# MainBoard.net
KiCad netlist of a schematic drawn in Altium Designer
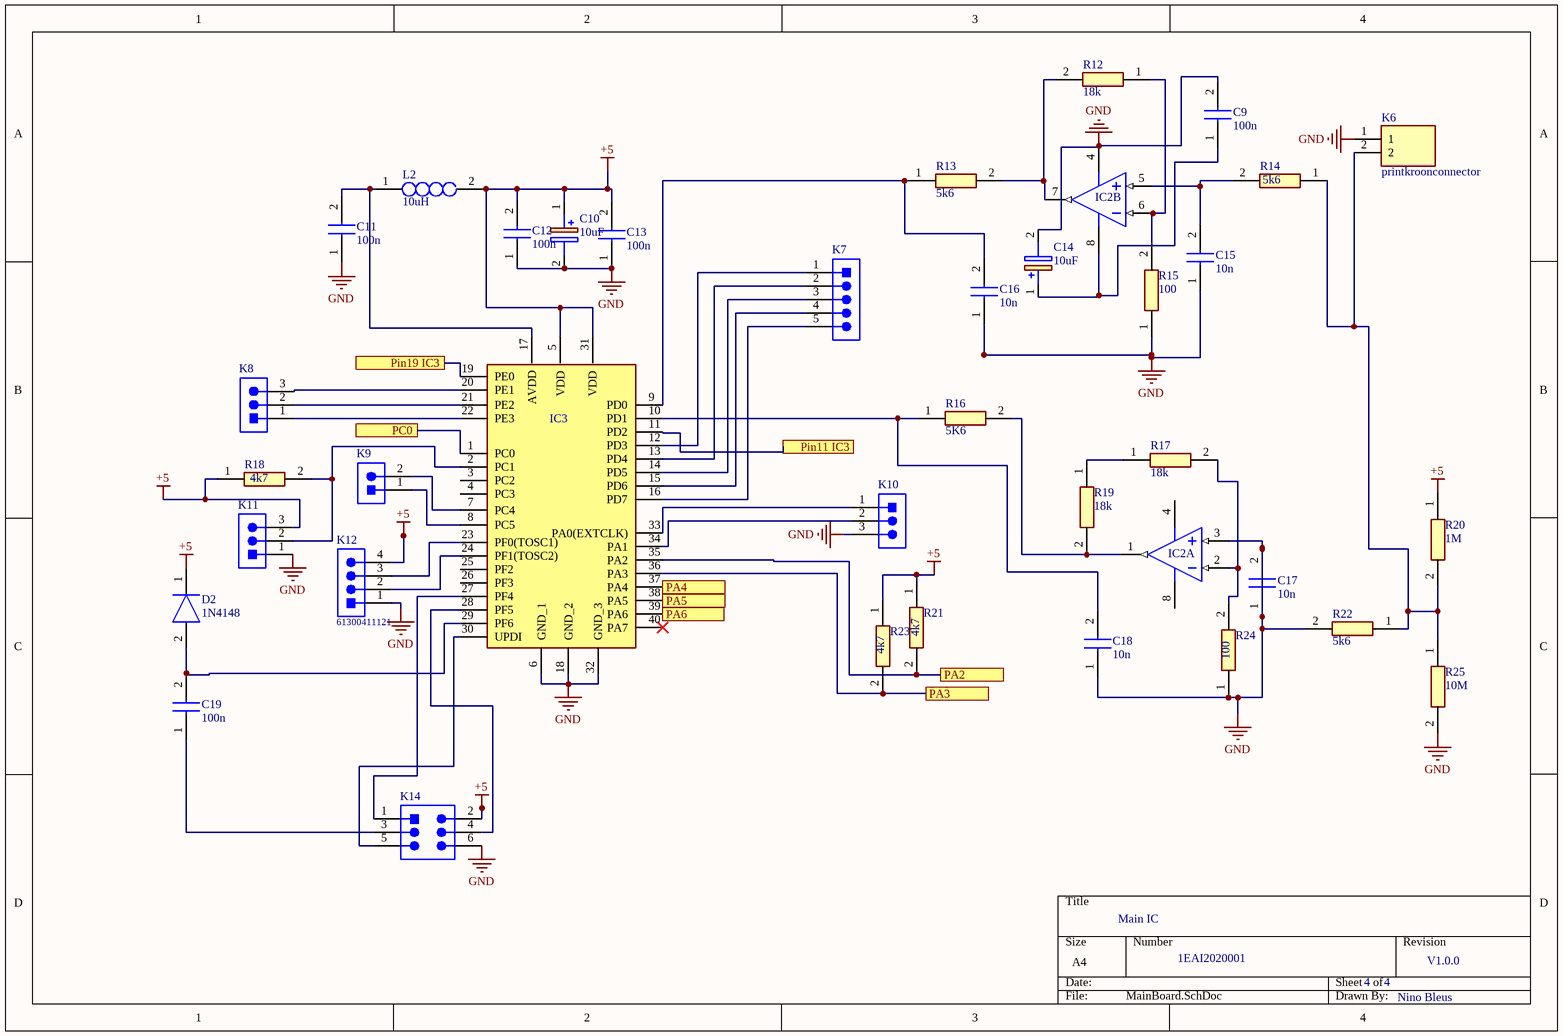
[diagram p0: MainBoard.SchDoc]

(export (version "E")
  (design (tool "Eeschema 10.0.6"))
  (components
    (comp (ref "C9")
      (value "100n")
      (footprint "SamacSys:CAPC2012X88N")
      (description "Capacitor")
      (fields (field (name "MANUFACTURER_PART_NUMBER") "C0805C103K5RACTU"))
      (libsource (lib "Schlib_soldeerbout") (part "0805 SMD capaciteit"))
    )
    (comp (ref "C10")
      (value "10uF")
      (footprint "SamacSys:CAPPRD250W45D630H850")
      (description "Capacitor Polarised")
      (fields (field (name "MANUFACTURER_PART_NUMBER") "ESS106M050AE2AA"))
      (libsource (lib "Schlib_soldeerbout") (part "10uF Capaciteit"))
    )
    (comp (ref "C11")
      (value "100n")
      (footprint "SamacSys:CAPC2012X88N")
      (description "Capacitor")
      (fields (field (name "MANUFACTURER_PART_NUMBER") "C0805C103K5RACTU"))
      (libsource (lib "Schlib_soldeerbout") (part "0805 SMD capaciteit"))
    )
    (comp (ref "C12")
      (value "100n")
      (footprint "SamacSys:CAPC2012X88N")
      (description "Capacitor")
      (fields (field (name "MANUFACTURER_PART_NUMBER") "C0805C103K5RACTU"))
      (libsource (lib "Schlib_soldeerbout") (part "0805 SMD capaciteit"))
    )
    (comp (ref "C13")
      (value "100n")
      (footprint "SamacSys:CAPC2012X88N")
      (description "Capacitor")
      (fields (field (name "MANUFACTURER_PART_NUMBER") "C0805C103K5RACTU"))
      (libsource (lib "Schlib_soldeerbout") (part "0805 SMD capaciteit"))
    )
    (comp (ref "C14")
      (value "10uF")
      (footprint "SamacSys:CAPPRD250W45D630H850")
      (description "Capacitor Polarised")
      (fields (field (name "MANUFACTURER_PART_NUMBER") "ESS106M050AE2AA"))
      (libsource (lib "") (part "10uF Capaciteit_1"))
    )
    (comp (ref "C15")
      (value "10n")
      (footprint "SamacSys:CAPC2012X88N")
      (description "Capacitor")
      (fields (field (name "MANUFACTURER_PART_NUMBER") "C0805C103K5RACTU"))
      (libsource (lib "Schlib_soldeerbout") (part "0805 SMD capaciteit"))
    )
    (comp (ref "C16")
      (value "10n")
      (footprint "SamacSys:CAPC2012X88N")
      (description "Capacitor")
      (fields (field (name "MANUFACTURER_PART_NUMBER") "C0805C103K5RACTU"))
      (libsource (lib "Schlib_soldeerbout") (part "0805 SMD capaciteit"))
    )
    (comp (ref "C17")
      (value "10n")
      (footprint "SamacSys:CAPC2012X88N")
      (description "Capacitor")
      (fields (field (name "MANUFACTURER_PART_NUMBER") "C0805C103K5RACTU"))
      (libsource (lib "Schlib_soldeerbout") (part "0805 SMD capaciteit"))
    )
    (comp (ref "C18")
      (value "10n")
      (footprint "SamacSys:CAPC2012X88N")
      (description "Capacitor")
      (fields (field (name "MANUFACTURER_PART_NUMBER") "C0805C103K5RACTU"))
      (libsource (lib "Schlib_soldeerbout") (part "0805 SMD capaciteit"))
    )
    (comp (ref "C19")
      (value "100n")
      (footprint "SamacSys:CAPC2012X88N")
      (description "Capacitor")
      (fields (field (name "MANUFACTURER_PART_NUMBER") "C0805C103K5RACTU"))
      (libsource (lib "Schlib_soldeerbout") (part "0805 SMD capaciteit"))
    )
    (comp (ref "D2")
      (value "1N4148")
      (footprint "SamacSys:DIOAD1165W56L425D185")
      (description "Diode")
      (libsource (lib "SamacSys") (part "1N4148"))
    )
    (comp (ref "IC2")
      (value "MCP6002-E/P")
      (footprint "PDIP300-P8")
      (description "None")
      (libsource (lib "Altium Content Vault") (part "AMP-OPA-MCP6002-IL8"))
    )
    (comp (ref "IC3")
      (value "ATMEGA4809-PF")
      (footprint "SamacSys:DIP1543W58P254L5175H635Q40N")
      (description "Integrated Circuit")
      (fields (field (name "MOUSER2 PART NUMBER") "556-ATMEGA4809-PF"))
      (libsource (lib "Schlib_soldeerbout") (part "ATMEGA4809-PF"))
    )
    (comp (ref "K6")
      (value "printkroonconnector")
      (footprint "SamacSys:1729128")
      (description "Connector")
      (fields (field (name "MANUFACTURER_PART_NUMBER") "1729128"))
      (libsource (lib "Schlib_soldeerbout") (part "printkroonconnector"))
    )
    (comp (ref "K7")
      (value "61300511121")
      (footprint "61300511121")
      (description "WR-PHD Pin Header, THT, pitch 2.54mm, Single Row, Vertical, 5p")
      (fields (field (name "MANUFACTURER") "Wurth Elektronik"))
      (libsource (lib "WR-PHD_Pin Header") (part "61300511121"))
    )
    (comp (ref "K8")
      (value "61300311121")
      (footprint "61300311121")
      (description "WR-PHD Pin Header, THT, pitch 2.54mm, Single Row, Vertical, 3p")
      (fields (field (name "MANUFACTURER") "Wurth Elektronik"))
      (libsource (lib "") (part "61300311121_1"))
    )
    (comp (ref "K9")
      (value "61300211121")
      (footprint "61300211121")
      (description "WR-PHD Pin Header, THT, pitch 2.54mm, Single Row, Vertical, 2p")
      (fields (field (name "MANUFACTURER") "Wurth Elektronik"))
      (libsource (lib "WR-PHD_Pin Header") (part "61300211121"))
    )
    (comp (ref "K10")
      (value "61300311121")
      (footprint "61300311121")
      (description "WR-PHD Pin Header, THT, pitch 2.54mm, Single Row, Vertical, 3p")
      (fields (field (name "MANUFACTURER") "Wurth Elektronik"))
      (libsource (lib "WR-PHD_Pin Header") (part "61300311121"))
    )
    (comp (ref "K11")
      (value "61300311121")
      (footprint "61300311121")
      (description "WR-PHD Pin Header, THT, pitch 2.54mm, Single Row, Vertical, 3p")
      (fields (field (name "MANUFACTURER") "Wurth Elektronik"))
      (libsource (lib "") (part "61300311121_1"))
    )
    (comp (ref "K12")
      (value "61300411121")
      (footprint "61300411121")
      (description "WR-PHD Pin Header, THT, pitch 2.54mm, Single Row, Vertical, 4p")
      (fields (field (name "MANUFACTURER") "Wurth Elektronik"))
      (libsource (lib "WR-PHD_Pin Header") (part "61300411121"))
    )
    (comp (ref "K14")
      (value "61300621121")
      (footprint "61300621121")
      (description "WR-PHD Pin Header, THT, pitch 2.54mm, Dual Row, Vertical, 6p")
      (fields (field (name "MANUFACTURER") "Wurth Elektronik"))
      (libsource (lib "WR-PHD_Pin Header") (part "61300621121"))
    )
    (comp (ref "L2")
      (value "10uH")
      (footprint "SamacSys:INDAD1827W51L711D279")
      (description "Inductor")
      (fields
        (field (name "MOUSER2 PART NUMBER") "542-78F100-RC")
        (field (name "MANUFACTURER_PART_NUMBER") "78F100J-RC")
      )
      (libsource (lib "Schlib_soldeerbout") (part "78F100J-RC"))
    )
    (comp (ref "R12")
      (value "18k")
      (footprint "SamacSys:RESC2012X65N")
      (description "Resistor")
      (fields (field (name "MANUFACTURER_PART_NUMBER") "ESR10EZPJ183"))
      (libsource (lib "") (part "ESR10EZPJ183_2"))
    )
    (comp (ref "R13")
      (value "5k6")
      (footprint "SamacSys:RESC2012X65N")
      (description "Resistor")
      (fields (field (name "MANUFACTURER_PART_NUMBER") "ESR10EZPJ183"))
      (libsource (lib "Schlib_soldeerbout") (part "ESR10EZPJ183"))
    )
    (comp (ref "R14")
      (value "5k6")
      (footprint "SamacSys:RESC2012X65N")
      (description "Resistor")
      (fields (field (name "MANUFACTURER_PART_NUMBER") "ESR10EZPJ183"))
      (libsource (lib "") (part "ESR10EZPJ183_2"))
    )
    (comp (ref "R15")
      (value "100")
      (footprint "SamacSys:RESC2012X65N")
      (description "Resistor")
      (fields (field (name "MANUFACTURER_PART_NUMBER") "ESR10EZPJ183"))
      (libsource (lib "") (part "ESR10EZPJ183_3"))
    )
    (comp (ref "R16")
      (value "5K6")
      (footprint "SamacSys:RESC2012X65N")
      (description "Resistor")
      (fields (field (name "MANUFACTURER_PART_NUMBER") "ESR10EZPJ183"))
      (libsource (lib "Schlib_soldeerbout") (part "ESR10EZPJ183"))
    )
    (comp (ref "R17")
      (value "18k")
      (footprint "SamacSys:RESC2012X65N")
      (description "Resistor")
      (fields (field (name "MANUFACTURER_PART_NUMBER") "ESR10EZPJ183"))
      (libsource (lib "Schlib_soldeerbout") (part "ESR10EZPJ183"))
    )
    (comp (ref "R18")
      (value "4k7")
      (footprint "SamacSys:RESC2012X65N")
      (description "Resistor")
      (fields (field (name "MANUFACTURER_PART_NUMBER") "ESR10EZPJ183"))
      (libsource (lib "Schlib_soldeerbout") (part "ESR10EZPJ183"))
    )
    (comp (ref "R19")
      (value "18k")
      (footprint "SamacSys:RESC2012X65N")
      (description "Resistor")
      (fields (field (name "MANUFACTURER_PART_NUMBER") "ESR10EZPJ183"))
      (libsource (lib "") (part "ESR10EZPJ183_1"))
    )
    (comp (ref "R20")
      (value "1M")
      (footprint "SamacSys:RESC2012X65N")
      (description "Resistor")
      (fields (field (name "MANUFACTURER_PART_NUMBER") "ESR10EZPJ183"))
      (libsource (lib "") (part "ESR10EZPJ183_1"))
    )
    (comp (ref "R21")
      (value "4k7")
      (footprint "SamacSys:RESC2012X65N")
      (description "Resistor")
      (fields (field (name "MANUFACTURER_PART_NUMBER") "ESR10EZPJ183"))
      (libsource (lib "") (part "ESR10EZPJ183_1"))
    )
    (comp (ref "R22")
      (value "5k6")
      (footprint "SamacSys:RESC2012X65N")
      (description "Resistor")
      (fields (field (name "MANUFACTURER_PART_NUMBER") "ESR10EZPJ183"))
      (libsource (lib "") (part "ESR10EZPJ183_2"))
    )
    (comp (ref "R23")
      (value "4k7")
      (footprint "SamacSys:RESC2012X65N")
      (description "Resistor")
      (fields (field (name "MANUFACTURER_PART_NUMBER") "ESR10EZPJ183"))
      (libsource (lib "") (part "ESR10EZPJ183_1"))
    )
    (comp (ref "R24")
      (value "100")
      (footprint "SamacSys:RESC2012X65N")
      (description "Resistor")
      (fields (field (name "MANUFACTURER_PART_NUMBER") "ESR10EZPJ183"))
      (libsource (lib "") (part "ESR10EZPJ183_3"))
    )
    (comp (ref "R25")
      (value "10M")
      (footprint "SamacSys:RESC2012X65N")
      (description "Resistor")
      (fields (field (name "MANUFACTURER_PART_NUMBER") "ESR10EZPJ183"))
      (libsource (lib "") (part "ESR10EZPJ183_1"))
    )
  )
  (nets
    (net (code "1") (name "+5") (class "Default")
      (node (ref "C10") (pin "1") (pinfunction "+_1") (pintype "passive"))
      (node (ref "C12") (pin "2") (pinfunction "2_2") (pintype "passive"))
      (node (ref "C13") (pin "2") (pinfunction "2_2") (pintype "passive"))
      (node (ref "D2") (pin "1") (pinfunction "K_1") (pintype "passive"))
      (node (ref "IC3") (pin "31") (pinfunction "VDD_31") (pintype "passive"))
      (node (ref "IC3") (pin "5") (pinfunction "VDD_5") (pintype "passive"))
      (node (ref "K11") (pin "3") (pinfunction "3_3") (pintype "passive"))
      (node (ref "K12") (pin "4") (pinfunction "4_4") (pintype "passive"))
      (node (ref "K14") (pin "2") (pinfunction "2_2") (pintype "passive"))
      (node (ref "L2") (pin "2") (pinfunction "2_2") (pintype "passive"))
      (node (ref "R18") (pin "1") (pinfunction "1_1") (pintype "passive"))
      (node (ref "R20") (pin "1") (pinfunction "1_1") (pintype "passive"))
      (node (ref "R21") (pin "1") (pinfunction "1_1") (pintype "passive"))
      (node (ref "R23") (pin "1") (pinfunction "1_1") (pintype "passive"))
    )
    (net (code "2") (name "/PA2") (class "Default")
      (node (ref "IC3") (pin "35") (pinfunction "PA2_35") (pintype "passive"))
      (node (ref "R21") (pin "2") (pinfunction "2_2") (pintype "passive"))
    )
    (net (code "3") (name "/PA3") (class "Default")
      (node (ref "IC3") (pin "36") (pinfunction "PA3_36") (pintype "passive"))
      (node (ref "R23") (pin "2") (pinfunction "2_2") (pintype "passive"))
    )
    (net (code "4") (name "/PA4") (class "Default")
      (node (ref "IC3") (pin "37") (pinfunction "PA4_37") (pintype "passive"))
    )
    (net (code "5") (name "/PA5") (class "Default")
      (node (ref "IC3") (pin "38") (pinfunction "PA5_38") (pintype "passive"))
    )
    (net (code "6") (name "/PA6") (class "Default")
      (node (ref "IC3") (pin "39") (pinfunction "PA6_39") (pintype "passive"))
    )
    (net (code "7") (name "/PC0") (class "Default")
      (node (ref "IC3") (pin "1") (pinfunction "PC0_1") (pintype "passive"))
    )
    (net (code "8") (name "/Pin11 IC3") (class "Default")
      (node (ref "IC3") (pin "11") (pinfunction "PD2_11") (pintype "passive"))
    )
    (net (code "9") (name "/Pin19 IC3") (class "Default")
      (node (ref "IC3") (pin "19") (pinfunction "PE0_19") (pintype "passive"))
    )
    (net (code "10") (name "GND") (class "Default")
      (node (ref "C10") (pin "2") (pinfunction "-_2") (pintype "passive"))
      (node (ref "C11") (pin "1") (pinfunction "1_1") (pintype "passive"))
      (node (ref "C12") (pin "1") (pinfunction "1_1") (pintype "passive"))
      (node (ref "C13") (pin "1") (pinfunction "1_1") (pintype "passive"))
      (node (ref "C14") (pin "2") (pinfunction "-_2") (pintype "passive"))
      (node (ref "C15") (pin "1") (pinfunction "1_1") (pintype "passive"))
      (node (ref "C16") (pin "1") (pinfunction "1_1") (pintype "passive"))
      (node (ref "C17") (pin "1") (pinfunction "1_1") (pintype "passive"))
      (node (ref "C17") (pin "2") (pinfunction "2_2") (pintype "passive"))
      (node (ref "C18") (pin "1") (pinfunction "1_1") (pintype "passive"))
      (node (ref "C9") (pin "2") (pinfunction "2_2") (pintype "passive"))
      (node (ref "IC2") (pin "3") (pinfunction "VINA+_3") (pintype "input"))
      (node (ref "IC2") (pin "4") (pinfunction "VSS_4") (pintype "power_in"))
      (node (ref "IC3") (pin "18") (pinfunction "GND_2_18") (pintype "passive"))
      (node (ref "IC3") (pin "32") (pinfunction "GND_3_32") (pintype "passive"))
      (node (ref "IC3") (pin "6") (pinfunction "GND_1_6") (pintype "passive"))
      (node (ref "K10") (pin "3") (pinfunction "3_3") (pintype "passive"))
      (node (ref "K11") (pin "1") (pinfunction "1_1") (pintype "passive"))
      (node (ref "K12") (pin "1") (pinfunction "1_1") (pintype "passive"))
      (node (ref "K14") (pin "6") (pinfunction "6_6") (pintype "passive"))
      (node (ref "K6") (pin "1") (pinfunction "1_1") (pintype "passive"))
      (node (ref "R15") (pin "1") (pinfunction "1_1") (pintype "passive"))
      (node (ref "R22") (pin "2") (pinfunction "2_2") (pintype "passive"))
      (node (ref "R24") (pin "1") (pinfunction "1_1") (pintype "passive"))
      (node (ref "R25") (pin "2") (pinfunction "2_2") (pintype "passive"))
    )
    (net (code "11") (name "Net-(C14-+)") (class "Default")
      (node (ref "C14") (pin "1") (pinfunction "+_1") (pintype "passive"))
      (node (ref "C9") (pin "1") (pinfunction "1_1") (pintype "passive"))
      (node (ref "IC2") (pin "8") (pinfunction "VDD_8") (pintype "power_in"))
    )
    (net (code "12") (name "Net-(C19-Pad1)") (class "Default")
      (node (ref "C19") (pin "1") (pinfunction "1_1") (pintype "passive"))
      (node (ref "K14") (pin "3") (pinfunction "3_3") (pintype "passive"))
    )
    (net (code "13") (name "Net-(D2-A)") (class "Default")
      (node (ref "C19") (pin "2") (pinfunction "2_2") (pintype "passive"))
      (node (ref "D2") (pin "2") (pinfunction "A_2") (pintype "passive"))
      (node (ref "IC3") (pin "29") (pinfunction "PF6_29") (pintype "passive"))
    )
    (net (code "14") (name "Net-(IC2A-VINA-)") (class "Default")
      (node (ref "IC2") (pin "2") (pinfunction "VINA-_2") (pintype "input"))
      (node (ref "R17") (pin "2") (pinfunction "2_2") (pintype "passive"))
      (node (ref "R24") (pin "2") (pinfunction "2_2") (pintype "passive"))
    )
    (net (code "15") (name "Net-(IC2A-VOUTA)") (class "Default")
      (node (ref "IC2") (pin "1") (pinfunction "VOUTA_1") (pintype "output"))
      (node (ref "R16") (pin "2") (pinfunction "2_2") (pintype "passive"))
      (node (ref "R19") (pin "2") (pinfunction "2_2") (pintype "passive"))
    )
    (net (code "16") (name "Net-(IC2B-VINB+)") (class "Default")
      (node (ref "C15") (pin "2") (pinfunction "2_2") (pintype "passive"))
      (node (ref "IC2") (pin "5") (pinfunction "VINB+_5") (pintype "input"))
      (node (ref "R14") (pin "2") (pinfunction "2_2") (pintype "passive"))
    )
    (net (code "17") (name "Net-(IC2B-VINB-)") (class "Default")
      (node (ref "IC2") (pin "6") (pinfunction "VINB-_6") (pintype "input"))
      (node (ref "R12") (pin "1") (pinfunction "1_1") (pintype "passive"))
      (node (ref "R15") (pin "2") (pinfunction "2_2") (pintype "passive"))
    )
    (net (code "18") (name "Net-(IC2B-VOUTB)") (class "Default")
      (node (ref "IC2") (pin "7") (pinfunction "VOUTB_7") (pintype "output"))
      (node (ref "R12") (pin "2") (pinfunction "2_2") (pintype "passive"))
      (node (ref "R13") (pin "2") (pinfunction "2_2") (pintype "passive"))
    )
    (net (code "19") (name "Net-(IC3-AVDD)") (class "Default")
      (node (ref "C11") (pin "2") (pinfunction "2_2") (pintype "passive"))
      (node (ref "IC3") (pin "17") (pinfunction "AVDD_17") (pintype "passive"))
      (node (ref "L2") (pin "1") (pinfunction "1_1") (pintype "passive"))
    )
    (net (code "20") (name "Net-(IC3-PA0(EXTCLK))") (class "Default")
      (node (ref "IC3") (pin "33") (pinfunction "PA0(EXTCLK)_33") (pintype "passive"))
      (node (ref "K10") (pin "1") (pinfunction "1_1") (pintype "passive"))
    )
    (net (code "21") (name "Net-(IC3-PA1)") (class "Default")
      (node (ref "IC3") (pin "34") (pinfunction "PA1_34") (pintype "passive"))
      (node (ref "K10") (pin "2") (pinfunction "2_2") (pintype "passive"))
    )
    (net (code "22") (name "Net-(IC3-PC1)") (class "Default")
      (node (ref "IC3") (pin "2") (pinfunction "PC1_2") (pintype "passive"))
      (node (ref "K11") (pin "2") (pinfunction "2_2") (pintype "passive"))
      (node (ref "R18") (pin "2") (pinfunction "2_2") (pintype "passive"))
    )
    (net (code "23") (name "Net-(IC3-PC4)") (class "Default")
      (node (ref "IC3") (pin "7") (pinfunction "PC4_7") (pintype "passive"))
      (node (ref "K9") (pin "2") (pinfunction "2_2") (pintype "passive"))
    )
    (net (code "24") (name "Net-(IC3-PC5)") (class "Default")
      (node (ref "IC3") (pin "8") (pinfunction "PC5_8") (pintype "passive"))
      (node (ref "K9") (pin "1") (pinfunction "1_1") (pintype "passive"))
    )
    (net (code "25") (name "Net-(IC3-PD0)") (class "Default")
      (node (ref "C16") (pin "2") (pinfunction "2_2") (pintype "passive"))
      (node (ref "IC3") (pin "9") (pinfunction "PD0_9") (pintype "passive"))
      (node (ref "R13") (pin "1") (pinfunction "1_1") (pintype "passive"))
    )
    (net (code "26") (name "Net-(IC3-PD1)") (class "Default")
      (node (ref "C18") (pin "2") (pinfunction "2_2") (pintype "passive"))
      (node (ref "IC3") (pin "10") (pinfunction "PD1_10") (pintype "passive"))
      (node (ref "R16") (pin "1") (pinfunction "1_1") (pintype "passive"))
    )
    (net (code "27") (name "Net-(IC3-PD3)") (class "Default")
      (node (ref "IC3") (pin "12") (pinfunction "PD3_12") (pintype "passive"))
      (node (ref "K7") (pin "1") (pinfunction "1_1") (pintype "passive"))
    )
    (net (code "28") (name "Net-(IC3-PD4)") (class "Default")
      (node (ref "IC3") (pin "13") (pinfunction "PD4_13") (pintype "passive"))
      (node (ref "K7") (pin "2") (pinfunction "2_2") (pintype "passive"))
    )
    (net (code "29") (name "Net-(IC3-PD5)") (class "Default")
      (node (ref "IC3") (pin "14") (pinfunction "PD5_14") (pintype "passive"))
      (node (ref "K7") (pin "3") (pinfunction "3_3") (pintype "passive"))
    )
    (net (code "30") (name "Net-(IC3-PD6)") (class "Default")
      (node (ref "IC3") (pin "15") (pinfunction "PD6_15") (pintype "passive"))
      (node (ref "K7") (pin "4") (pinfunction "4_4") (pintype "passive"))
    )
    (net (code "31") (name "Net-(IC3-PD7)") (class "Default")
      (node (ref "IC3") (pin "16") (pinfunction "PD7_16") (pintype "passive"))
      (node (ref "K7") (pin "5") (pinfunction "5_5") (pintype "passive"))
    )
    (net (code "32") (name "Net-(IC3-PE1)") (class "Default")
      (node (ref "IC3") (pin "20") (pinfunction "PE1_20") (pintype "passive"))
      (node (ref "K8") (pin "3") (pinfunction "3_3") (pintype "passive"))
    )
    (net (code "33") (name "Net-(IC3-PE2)") (class "Default")
      (node (ref "IC3") (pin "21") (pinfunction "PE2_21") (pintype "passive"))
      (node (ref "K8") (pin "2") (pinfunction "2_2") (pintype "passive"))
    )
    (net (code "34") (name "Net-(IC3-PE3)") (class "Default")
      (node (ref "IC3") (pin "22") (pinfunction "PE3_22") (pintype "passive"))
      (node (ref "K8") (pin "1") (pinfunction "1_1") (pintype "passive"))
    )
    (net (code "35") (name "Net-(IC3-PF0(TOSC1))") (class "Default")
      (node (ref "IC3") (pin "23") (pinfunction "PF0(TOSC1)_23") (pintype "passive"))
      (node (ref "K12") (pin "3") (pinfunction "3_3") (pintype "passive"))
    )
    (net (code "36") (name "Net-(IC3-PF1(TOSC2))") (class "Default")
      (node (ref "IC3") (pin "24") (pinfunction "PF1(TOSC2)_24") (pintype "passive"))
      (node (ref "K12") (pin "2") (pinfunction "2_2") (pintype "passive"))
    )
    (net (code "37") (name "Net-(IC3-PF4)") (class "Default")
      (node (ref "IC3") (pin "27") (pinfunction "PF4_27") (pintype "passive"))
      (node (ref "K14") (pin "1") (pinfunction "1_1") (pintype "passive"))
    )
    (net (code "38") (name "Net-(IC3-PF5)") (class "Default")
      (node (ref "IC3") (pin "28") (pinfunction "PF5_28") (pintype "passive"))
      (node (ref "K14") (pin "4") (pinfunction "4_4") (pintype "passive"))
    )
    (net (code "39") (name "Net-(IC3-UPDI)") (class "Default")
      (node (ref "IC3") (pin "30") (pinfunction "UPDI_30") (pintype "passive"))
      (node (ref "K14") (pin "5") (pinfunction "5_5") (pintype "passive"))
    )
    (net (code "40") (name "Net-(K6-Pad2)") (class "Default")
      (node (ref "K6") (pin "2") (pinfunction "2_2") (pintype "passive"))
      (node (ref "R14") (pin "1") (pinfunction "1_1") (pintype "passive"))
      (node (ref "R20") (pin "2") (pinfunction "2_2") (pintype "passive"))
      (node (ref "R22") (pin "1") (pinfunction "1_1") (pintype "passive"))
      (node (ref "R25") (pin "1") (pinfunction "1_1") (pintype "passive"))
    )
    (net (code "41") (name "Net-(R17-Pad1)") (class "Default")
      (node (ref "R17") (pin "1") (pinfunction "1_1") (pintype "passive"))
      (node (ref "R19") (pin "1") (pinfunction "1_1") (pintype "passive"))
    )
    (net (code "42") (name "unconnected-(IC2A-VDD-Pad8)") (class "Default")
      (node (ref "IC2") (pin "8") (pinfunction "VDD_8") (pintype "power_in"))
    )
    (net (code "43") (name "unconnected-(IC2A-VSS-Pad4)") (class "Default")
      (node (ref "IC2") (pin "4") (pinfunction "VSS_4") (pintype "power_in"))
    )
    (net (code "44") (name "unconnected-(IC3-PA7-Pad40)") (class "Default")
      (node (ref "IC3") (pin "40") (pinfunction "PA7_40") (pintype "passive+no_connect"))
    )
    (net (code "45") (name "unconnected-(IC3-PC2-Pad3)") (class "Default")
      (node (ref "IC3") (pin "3") (pinfunction "PC2_3") (pintype "passive"))
    )
    (net (code "46") (name "unconnected-(IC3-PC3-Pad4)") (class "Default")
      (node (ref "IC3") (pin "4") (pinfunction "PC3_4") (pintype "passive"))
    )
    (net (code "47") (name "unconnected-(IC3-PF2-Pad25)") (class "Default")
      (node (ref "IC3") (pin "25") (pinfunction "PF2_25") (pintype "passive"))
    )
    (net (code "48") (name "unconnected-(IC3-PF3-Pad26)") (class "Default")
      (node (ref "IC3") (pin "26") (pinfunction "PF3_26") (pintype "passive"))
    )
  )
)
